# PowerSupply.net
KiCad netlist of a schematic drawn in Altium Designer
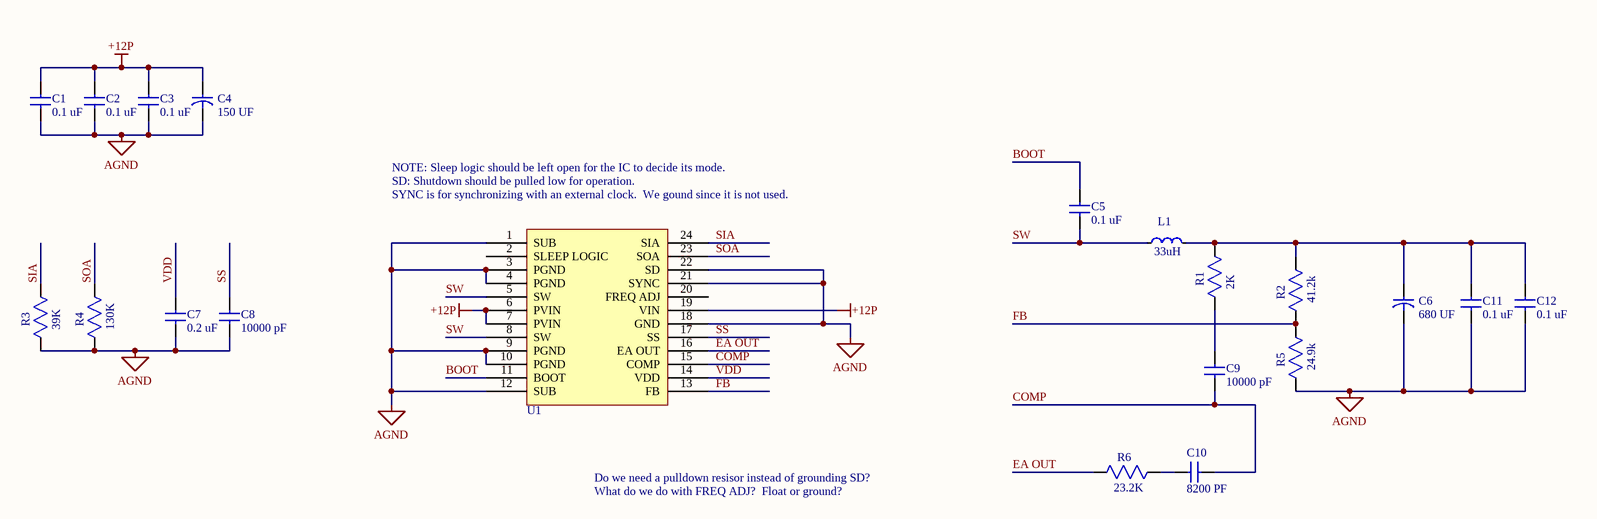
[diagram p0: PowerSupply.SchDoc]

(export (version "E")
  (design (tool "Eeschema 10.0.6"))
  (components
    (comp (ref "C1")
      (value "0.1 uF")
      (footprint "0805")
      (description "CAP CERM 0.1uF")
      (fields
        (field (name "MANUFACTURER") "Yageo")
        (field (name "Comment") "CAP 0.1uF")
        (field (name "SVP CREATOR") "Brett Paulsen")
      )
      (libsource (lib "c3_SchLib") (part "C_0805_0.1uF_1"))
    )
    (comp (ref "C2")
      (value "0.1 uF")
      (footprint "0805")
      (description "CAP CERM 0.1uF")
      (fields
        (field (name "MANUFACTURER") "Yageo")
        (field (name "Comment") "CAP 0.1uF")
        (field (name "SVP CREATOR") "Brett Paulsen")
      )
      (libsource (lib "c3_SchLib") (part "C_0805_0.1uF_1"))
    )
    (comp (ref "C3")
      (value "0.1 uF")
      (footprint "0805")
      (description "CAP CERM 0.1uF")
      (fields
        (field (name "MANUFACTURER") "Yageo")
        (field (name "Comment") "CAP 0.1uF")
        (field (name "SVP CREATOR") "Brett Paulsen")
      )
      (libsource (lib "c3_SchLib") (part "C_0805_0.1uF_1"))
    )
    (comp (ref "C4")
      (value "150 UF")
      (footprint "CAP_NICHICON_R7")
      (description "CAP POLY 150UF 20V HT 125C RAD")
      (fields
        (field (name "MANUFACTURER") "Nichicon")
        (field (name "TOLERANCE") "20%")
        (field (name "SVP CREATOR") "Jonathan Nutzmann")
      )
      (libsource (lib "c3_SchLib") (part "C_POLY_150UF"))
    )
    (comp (ref "C5")
      (value "0.1 uF")
      (footprint "0805")
      (description "CAP CERM 0.1uF")
      (fields
        (field (name "MANUFACTURER") "Yageo")
        (field (name "Comment") "CAP 0.1uF")
        (field (name "SVP CREATOR") "Brett Paulsen")
      )
      (libsource (lib "c3_SchLib") (part "C_0805_0.1uF_1"))
    )
    (comp (ref "C6")
      (value "680 UF")
      (footprint "CAP_NICHICON_R7")
      (description "CAP POLY 680UF 10V LOW ESR RAD")
      (fields
        (field (name "MANUFACTURER") "Nichicon")
        (field (name "Comment") "CAP POLY 680UF")
        (field (name "SVP CREATOR") "Jonathan Nutzmann")
      )
      (libsource (lib "c3_SchLib") (part "C_POLY_680UF_10V"))
    )
    (comp (ref "C7")
      (value "0.2 uF")
      (footprint "0805")
      (description "CAP CERM 0.2uF")
      (fields (field (name "Comment") "CAP 0.2uF") (field (name "SVP CREATOR") "Brett Paulsen"))
      (libsource (lib "c3_SchLib") (part "C_0805_0.2uF"))
    )
    (comp (ref "C8")
      (value "10000 pF")
      (footprint "0805")
      (description "CAP CERM 10000PF")
      (fields
        (field (name "MANUFACTURER") "AVX")
        (field (name "Comment") "CAP 10000pF")
        (field (name "SVP CREATOR") "Jonathan Nutzmann")
      )
      (libsource (lib "c3_SchLib") (part "C_0805_10000pF"))
    )
    (comp (ref "C9")
      (value "10000 pF")
      (footprint "0805")
      (description "CAP CERM 10000PF")
      (fields
        (field (name "MANUFACTURER") "AVX")
        (field (name "Comment") "CAP 10000pF")
        (field (name "SVP CREATOR") "Jonathan Nutzmann")
      )
      (libsource (lib "c3_SchLib") (part "C_0805_10000pF"))
    )
    (comp (ref "C10")
      (value "8200 PF")
      (footprint "0805")
      (description "CAP CERM 8200 PF")
      (fields (field (name "Comment") "CAP 8200 PF") (field (name "SVP CREATOR") "Jonathan Nutzmann"))
      (libsource (lib "c3_SchLib") (part "C_0805_8200PF_100V"))
    )
    (comp (ref "C11")
      (value "0.1 uF")
      (footprint "0805")
      (description "CAP CERM 0.1uF")
      (fields
        (field (name "MANUFACTURER") "Yageo")
        (field (name "Comment") "CAP 0.1uF")
        (field (name "SVP CREATOR") "Brett Paulsen")
      )
      (libsource (lib "c3_SchLib") (part "C_0805_0.1uF"))
    )
    (comp (ref "C12")
      (value "0.1 uF")
      (footprint "0805")
      (description "CAP CERM 0.1uF")
      (fields
        (field (name "MANUFACTURER") "Yageo")
        (field (name "Comment") "CAP 0.1uF")
        (field (name "SVP CREATOR") "Brett Paulsen")
      )
      (libsource (lib "c3_SchLib") (part "C_0805_0.1uF"))
    )
    (comp (ref "L1")
      (value "33uH")
      (footprint "L_SRR1210")
      (description "INDUCTOR PWR 33UH 20% SHIELD SMD")
      (fields
        (field (name "MANUFACTURER") "Bourns Inc")
        (field (name "Comment") "L_33uH_20%")
        (field (name "SVP CREATOR") "Jonathan Nutzmann")
      )
      (libsource (lib "c3_SchLib") (part "L_33uH_20%"))
    )
    (comp (ref "R1")
      (value "2K")
      (footprint "0805")
      (description "RES 2K OHM 1/8W 1% 0805 SMD")
      (fields (field (name "Comment") "R_0805_2K_1%") (field (name "SVP CREATOR") "Jonathan Nutzmann"))
      (libsource (lib "c3_SchLib") (part "R_0805_2K_1%_2K"))
    )
    (comp (ref "R2")
      (value "41.2k")
      (footprint "0805")
      (description "RES 41.2K OHM 1/8W 1% 0805 SMD")
      (fields (field (name "Comment") "R_0805_41.2K_1%") (field (name "SVP CREATOR") "Jonathan Nutzmann"))
      (libsource (lib "c3_SchLib") (part "R_0805_41.2K_1%"))
    )
    (comp (ref "R3")
      (value "39K")
      (footprint "0805")
      (description "RES 39K OHM 1/8W 1% 0805 SMD")
      (fields (field (name "Comment") "R_0805_39K_1%") (field (name "SVP CREATOR") "Jonathan Nutzmann"))
      (libsource (lib "c3_SchLib") (part "R_0805_39K_1%_5"))
    )
    (comp (ref "R4")
      (value "130K")
      (footprint "0805")
      (description "RES 130K OHM 1/8W 1% 0805 SMD")
      (fields (field (name "Comment") "R_0805_130K_1%") (field (name "SVP CREATOR") "Jonathan Nutzmann"))
      (libsource (lib "c3_SchLib") (part "R_0805_130K_1%"))
    )
    (comp (ref "R5")
      (value "24.9k")
      (footprint "0805")
      (description "RES 24.9K OHM 1/8W 1% 0805 SMD")
      (fields (field (name "Comment") "R_0805_24.9k_1%") (field (name "SVP CREATOR") "Jonathan Nutzmann"))
      (libsource (lib "c3_SchLib") (part "R_0805_24.9k_1%"))
    )
    (comp (ref "R6")
      (value "23.2K")
      (footprint "0805")
      (description "RES 23.2K OHM 1/8W 1% 0805 SMD")
      (fields (field (name "Comment") "R_0805_23.2K_1%") (field (name "SVP CREATOR") "Jonathan Nutzmann"))
      (libsource (lib "c3_SchLib") (part "R_0805_23.2K_1%"))
    )
    (comp (ref "U1")
      (value "LM2650 DC/DC Converter")
      (footprint "SOIC127P1030X265-24N")
      (description "IC CONVERTER SYNCH DC/DC 24-SOIC")
      (fields
        (field (name "MANUFACTURER") "National Semiconductor")
        (field (name "SVP CREATOR") "Jonathan Nutzmann")
      )
      (libsource (lib "c3_SchLib") (part "U_LM2650"))
    )
  )
  (nets
    (net (code "1") (name "+12P") (class "Default")
      (node (ref "C1") (pin "1") (pinfunction "1_1") (pintype "passive"))
      (node (ref "C2") (pin "1") (pinfunction "1_1") (pintype "passive"))
      (node (ref "C3") (pin "1") (pinfunction "1_1") (pintype "passive"))
      (node (ref "C4") (pin "1") (pinfunction "1_1") (pintype "passive"))
      (node (ref "U1") (pin "19") (pinfunction "VIN_19") (pintype "passive"))
      (node (ref "U1") (pin "6") (pinfunction "PVIN_6") (pintype "passive"))
      (node (ref "U1") (pin "7") (pinfunction "PVIN_7") (pintype "passive"))
    )
    (net (code "2") (name "/BOOT") (class "Default")
      (node (ref "C5") (pin "1") (pinfunction "1_1") (pintype "passive"))
      (node (ref "U1") (pin "11") (pinfunction "BOOT_11") (pintype "passive"))
    )
    (net (code "3") (name "/COMP") (class "Default")
      (node (ref "C10") (pin "1") (pinfunction "1_1") (pintype "passive"))
      (node (ref "C9") (pin "2") (pinfunction "2_2") (pintype "passive"))
      (node (ref "U1") (pin "15") (pinfunction "COMP_15") (pintype "passive"))
    )
    (net (code "4") (name "/EA OUT") (class "Default")
      (node (ref "R6") (pin "2") (pinfunction "2_2") (pintype "passive"))
      (node (ref "U1") (pin "16") (pinfunction "EA_OUT_16") (pintype "passive"))
    )
    (net (code "5") (name "/FB") (class "Default")
      (node (ref "R2") (pin "2") (pinfunction "2_2") (pintype "passive"))
      (node (ref "R5") (pin "1") (pinfunction "1_1") (pintype "passive"))
      (node (ref "U1") (pin "13") (pinfunction "FB_13") (pintype "passive"))
    )
    (net (code "6") (name "/SIA") (class "Default")
      (node (ref "R3") (pin "1") (pinfunction "1_1") (pintype "passive"))
      (node (ref "U1") (pin "24") (pinfunction "SIA_24") (pintype "passive"))
    )
    (net (code "7") (name "/SOA") (class "Default")
      (node (ref "R4") (pin "1") (pinfunction "1_1") (pintype "passive"))
      (node (ref "U1") (pin "23") (pinfunction "SOA_23") (pintype "passive"))
    )
    (net (code "8") (name "/SS") (class "Default")
      (node (ref "C8") (pin "1") (pinfunction "1_1") (pintype "passive"))
      (node (ref "U1") (pin "17") (pinfunction "SS_17") (pintype "passive"))
    )
    (net (code "9") (name "/SW") (class "Default")
      (node (ref "C5") (pin "2") (pinfunction "2_2") (pintype "passive"))
      (node (ref "L1") (pin "1") (pinfunction "1_1") (pintype "passive"))
      (node (ref "U1") (pin "5") (pinfunction "SW_5") (pintype "passive"))
      (node (ref "U1") (pin "8") (pinfunction "SW_8") (pintype "passive"))
    )
    (net (code "10") (name "/VDD") (class "Default")
      (node (ref "C7") (pin "1") (pinfunction "1_1") (pintype "passive"))
      (node (ref "U1") (pin "14") (pinfunction "VDD_14") (pintype "passive"))
    )
    (net (code "11") (name "AGND") (class "Default")
      (node (ref "C1") (pin "2") (pinfunction "2_2") (pintype "passive"))
      (node (ref "C11") (pin "2") (pinfunction "2_2") (pintype "passive"))
      (node (ref "C12") (pin "2") (pinfunction "2_2") (pintype "passive"))
      (node (ref "C2") (pin "2") (pinfunction "2_2") (pintype "passive"))
      (node (ref "C3") (pin "2") (pinfunction "2_2") (pintype "passive"))
      (node (ref "C4") (pin "2") (pinfunction "2_2") (pintype "passive"))
      (node (ref "C6") (pin "2") (pinfunction "2_2") (pintype "passive"))
      (node (ref "C7") (pin "2") (pinfunction "2_2") (pintype "passive"))
      (node (ref "C8") (pin "2") (pinfunction "2_2") (pintype "passive"))
      (node (ref "R3") (pin "2") (pinfunction "2_2") (pintype "passive"))
      (node (ref "R4") (pin "2") (pinfunction "2_2") (pintype "passive"))
      (node (ref "R5") (pin "2") (pinfunction "2_2") (pintype "passive"))
      (node (ref "U1") (pin "1") (pinfunction "SUB_1") (pintype "passive"))
      (node (ref "U1") (pin "10") (pinfunction "PGND_10") (pintype "passive"))
      (node (ref "U1") (pin "12") (pinfunction "SUB_12") (pintype "passive"))
      (node (ref "U1") (pin "18") (pinfunction "GND_18") (pintype "passive"))
      (node (ref "U1") (pin "21") (pinfunction "SYNC_21") (pintype "passive"))
      (node (ref "U1") (pin "22") (pinfunction "SD_22") (pintype "passive"))
      (node (ref "U1") (pin "3") (pinfunction "PGND_3") (pintype "passive"))
      (node (ref "U1") (pin "4") (pinfunction "PGND_4") (pintype "passive"))
      (node (ref "U1") (pin "9") (pinfunction "PGND_9") (pintype "passive"))
    )
    (net (code "12") (name "Net-(C9-Pad1)") (class "Default")
      (node (ref "C9") (pin "1") (pinfunction "1_1") (pintype "passive"))
      (node (ref "R1") (pin "2") (pinfunction "2_2") (pintype "passive"))
    )
    (net (code "13") (name "Net-(C10-Pad2)") (class "Default")
      (node (ref "C10") (pin "2") (pinfunction "2_2") (pintype "passive"))
      (node (ref "R6") (pin "1") (pinfunction "1_1") (pintype "passive"))
    )
    (net (code "14") (name "Net-(C11-Pad1)") (class "Default")
      (node (ref "C11") (pin "1") (pinfunction "1_1") (pintype "passive"))
      (node (ref "C12") (pin "1") (pinfunction "1_1") (pintype "passive"))
      (node (ref "C6") (pin "1") (pinfunction "1_1") (pintype "passive"))
      (node (ref "L1") (pin "2") (pinfunction "2_2") (pintype "passive"))
      (node (ref "R1") (pin "1") (pinfunction "1_1") (pintype "passive"))
      (node (ref "R2") (pin "1") (pinfunction "1_1") (pintype "passive"))
    )
    (net (code "15") (name "unconnected-(U1-FREQ_ADJ-Pad20)") (class "Default")
      (node (ref "U1") (pin "20") (pinfunction "FREQ_ADJ_20") (pintype "passive"))
    )
    (net (code "16") (name "unconnected-(U1-SLEEP_LOGIC-Pad2)") (class "Default")
      (node (ref "U1") (pin "2") (pinfunction "SLEEP_LOGIC_2") (pintype "passive"))
    )
  )
)
